# Buffers.net
KiCad netlist of a schematic drawn in Altium Designer
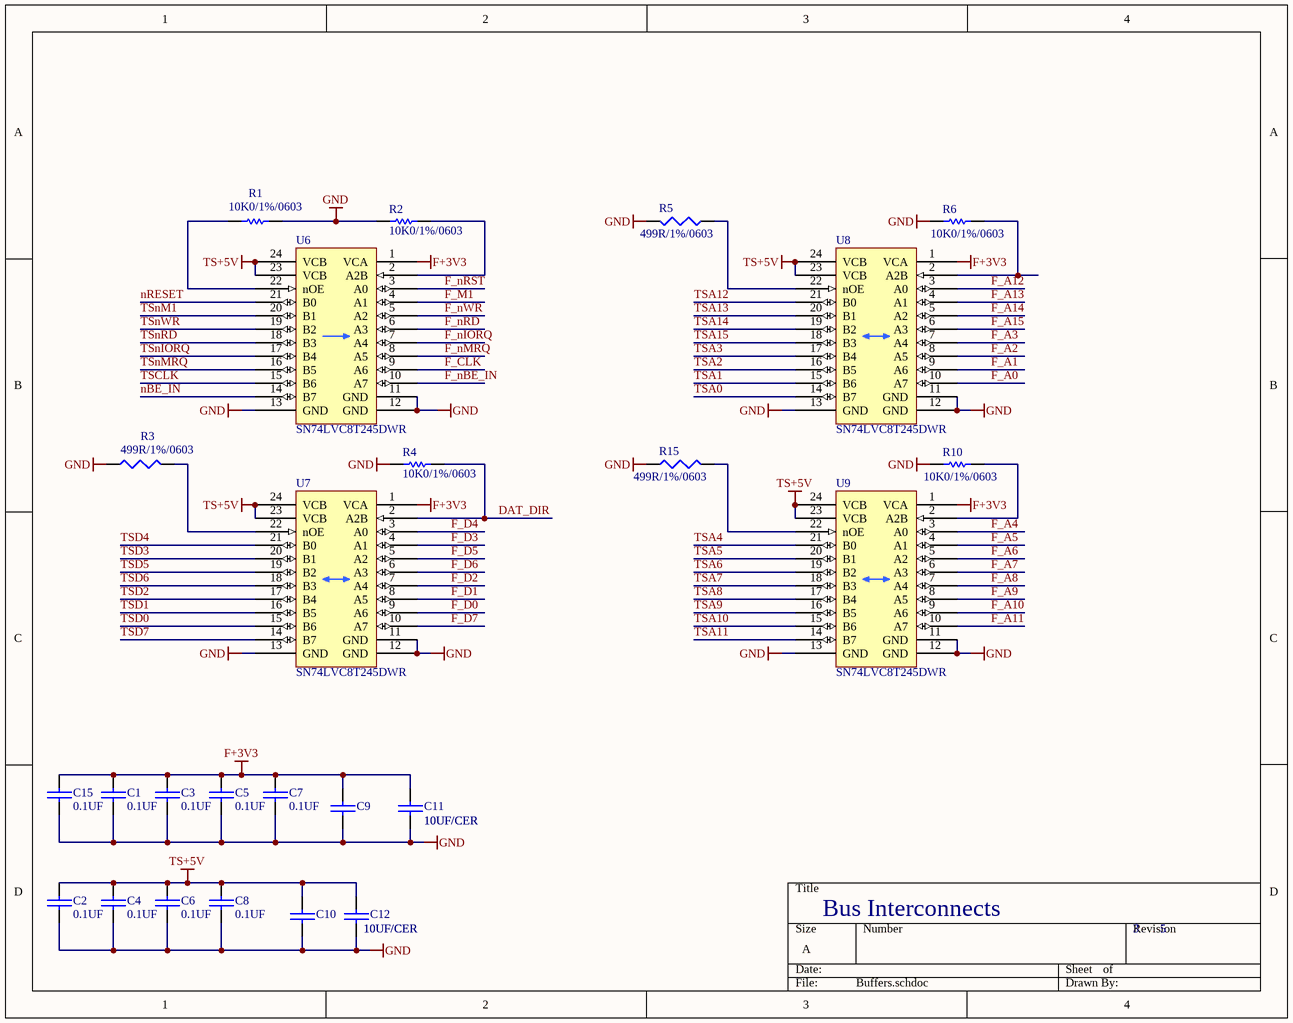
[diagram p0: Buffers.schdoc]

(export (version "E")
  (design (tool "Eeschema 10.0.6"))
  (components
    (comp (ref "C1")
      (value "0.1UF")
      (footprint "0603")
      (description "CAP .10UF 16V CERAMIC X7R 0603")
      (fields (field (name "MFG") "Kemet"))
      (libsource (lib "C64Interface") (part "0.1UF"))
    )
    (comp (ref "C2")
      (value "0.1UF")
      (footprint "0603")
      (description "CAP .10UF 16V CERAMIC X7R 0603")
      (fields (field (name "MFG") "Kemet"))
      (libsource (lib "C64Interface") (part "0.1UF"))
    )
    (comp (ref "C3")
      (value "0.1UF")
      (footprint "0603")
      (description "CAP .10UF 16V CERAMIC X7R 0603")
      (fields (field (name "MFG") "Kemet"))
      (libsource (lib "C64Interface") (part "0.1UF"))
    )
    (comp (ref "C4")
      (value "0.1UF")
      (footprint "0603")
      (description "CAP .10UF 16V CERAMIC X7R 0603")
      (fields (field (name "MFG") "Kemet"))
      (libsource (lib "C64Interface") (part "0.1UF"))
    )
    (comp (ref "C5")
      (value "0.1UF")
      (footprint "0603")
      (description "CAP .10UF 16V CERAMIC X7R 0603")
      (fields (field (name "MFG") "Kemet"))
      (libsource (lib "C64Interface") (part "0.1UF"))
    )
    (comp (ref "C6")
      (value "0.1UF")
      (footprint "0603")
      (description "CAP .10UF 16V CERAMIC X7R 0603")
      (fields (field (name "MFG") "Kemet"))
      (libsource (lib "C64Interface") (part "0.1UF"))
    )
    (comp (ref "C7")
      (value "0.1UF")
      (footprint "0603")
      (description "CAP .10UF 16V CERAMIC X7R 0603")
      (fields (field (name "MFG") "Kemet"))
      (libsource (lib "C64Interface") (part "0.1UF"))
    )
    (comp (ref "C8")
      (value "0.1UF")
      (footprint "0603")
      (description "CAP .10UF 16V CERAMIC X7R 0603")
      (fields (field (name "MFG") "Kemet"))
      (libsource (lib "C64Interface") (part "0.1UF"))
    )
    (comp (ref "C9")
      (value "10UF/CER")
      (footprint "0805")
      (description "10µF ±10% 25V Ceramic Capacitor X7S 0805")
      (fields (field (name "MFG") "Murata"))
      (libsource (lib "Capacitors") (part "10UF/CER"))
    )
    (comp (ref "C10")
      (value "10UF/CER")
      (footprint "0805")
      (description "10µF ±10% 25V Ceramic Capacitor X7S 0805")
      (fields (field (name "MFG") "Murata"))
      (libsource (lib "Capacitors") (part "10UF/CER"))
    )
    (comp (ref "C11")
      (value "10UF/CER")
      (footprint "0805")
      (description "10µF ±10% 25V Ceramic Capacitor X7S 0805")
      (fields (field (name "MFG") "Murata"))
      (libsource (lib "Capacitors") (part "10UF/CER"))
    )
    (comp (ref "C12")
      (value "10UF/CER")
      (footprint "0805")
      (description "10µF ±10% 25V Ceramic Capacitor X7S 0805")
      (fields (field (name "MFG") "Murata"))
      (libsource (lib "Capacitors") (part "10UF/CER"))
    )
    (comp (ref "C15")
      (value "0.1UF")
      (footprint "0603")
      (description "CAP .10UF 16V CERAMIC X7R 0603")
      (fields (field (name "MFG") "Kemet"))
      (libsource (lib "C64Interface") (part "0.1UF"))
    )
    (comp (ref "R1")
      (value "10K0/1%/0603")
      (footprint "0603")
      (description "10k Ohm ±1% 0.1W, 1/10W Chip Resistor 0603 (1608 Metric) Moisture Resistant Thick Film")
      (fields (field (name "MFG") "Yageo"))
      (libsource (lib "Resistors") (part "RES10K0"))
    )
    (comp (ref "R2")
      (value "10K0/1%/0603")
      (footprint "0603")
      (description "10k Ohm ±1% 0.1W, 1/10W Chip Resistor 0603 (1608 Metric) Moisture Resistant Thick Film")
      (fields (field (name "MFG") "Yageo"))
      (libsource (lib "Resistors") (part "RES10K0"))
    )
    (comp (ref "R3")
      (value "499R/1%/0603")
      (footprint "0603")
      (description "499 Ohms ±1% 0.1W, 1/10W Chip Resistor 0603 (1608 Metric) Moisture Resistant Thick Film")
      (fields (field (name "MFG") "Yeago"))
      (libsource (lib "Resistors") (part "499R/1%/0603"))
    )
    (comp (ref "R4")
      (value "10K0/1%/0603")
      (footprint "0603")
      (description "10k Ohm ±1% 0.1W, 1/10W Chip Resistor 0603 (1608 Metric) Moisture Resistant Thick Film")
      (fields (field (name "MFG") "Yageo"))
      (libsource (lib "Resistors") (part "RES10K0"))
    )
    (comp (ref "R5")
      (value "499R/1%/0603")
      (footprint "0603")
      (description "499 Ohms ±1% 0.1W, 1/10W Chip Resistor 0603 (1608 Metric) Moisture Resistant Thick Film")
      (fields (field (name "MFG") "Yeago"))
      (libsource (lib "Resistors") (part "499R/1%/0603"))
    )
    (comp (ref "R6")
      (value "10K0/1%/0603")
      (footprint "0603")
      (description "10k Ohm ±1% 0.1W, 1/10W Chip Resistor 0603 (1608 Metric) Moisture Resistant Thick Film")
      (fields (field (name "MFG") "Yageo"))
      (libsource (lib "Resistors") (part "RES10K0"))
    )
    (comp (ref "R10")
      (value "10K0/1%/0603")
      (footprint "0603")
      (description "10k Ohm ±1% 0.1W, 1/10W Chip Resistor 0603 (1608 Metric) Moisture Resistant Thick Film")
      (fields (field (name "MFG") "Yageo"))
      (libsource (lib "Resistors") (part "RES10K0"))
    )
    (comp (ref "R15")
      (value "499R/1%/0603")
      (footprint "0603")
      (description "499 Ohms ±1% 0.1W, 1/10W Chip Resistor 0603 (1608 Metric) Moisture Resistant Thick Film")
      (fields (field (name "MFG") "Yeago"))
      (libsource (lib "Resistors") (part "499R/1%/0603"))
    )
    (comp (ref "U6")
      (value "SN74LVC8T245DWR")
      (footprint "SOL-24")
      (description "Voltage Level Translator Bidirectional 1 Circuit 8 Channel 24-SOIC")
      (fields (field (name "MFG") "TI"))
      (libsource (lib "DigitalIC") (part "SN74LVC8T245DWR"))
    )
    (comp (ref "U7")
      (value "SN74LVC8T245DWR")
      (footprint "SOL-24")
      (description "Voltage Level Translator Bidirectional 1 Circuit 8 Channel 24-SOIC")
      (fields (field (name "MFG") "TI"))
      (libsource (lib "DigitalIC") (part "SN74LVC8T245DWR"))
    )
    (comp (ref "U8")
      (value "SN74LVC8T245DWR")
      (footprint "SOL-24")
      (description "Voltage Level Translator Bidirectional 1 Circuit 8 Channel 24-SOIC")
      (fields (field (name "MFG") "TI"))
      (libsource (lib "DigitalIC") (part "SN74LVC8T245DWR"))
    )
    (comp (ref "U9")
      (value "SN74LVC8T245DWR")
      (footprint "SOL-24")
      (description "Voltage Level Translator Bidirectional 1 Circuit 8 Channel 24-SOIC")
      (fields (field (name "MFG") "TI"))
      (libsource (lib "DigitalIC") (part "SN74LVC8T245DWR"))
    )
  )
  (nets
    (net (code "1") (name "/DAT_DIR") (class "Default")
      (node (ref "R4") (pin "2") (pinfunction "2_2") (pintype "passive"))
      (node (ref "U7") (pin "2") (pinfunction "A2B_2") (pintype "input"))
    )
    (net (code "2") (name "/F_A0") (class "Default")
      (node (ref "U8") (pin "10") (pinfunction "A7_10") (pintype "bidirectional"))
    )
    (net (code "3") (name "/F_A1") (class "Default")
      (node (ref "U8") (pin "9") (pinfunction "A6_9") (pintype "bidirectional"))
    )
    (net (code "4") (name "/F_A2") (class "Default")
      (node (ref "U8") (pin "8") (pinfunction "A5_8") (pintype "bidirectional"))
    )
    (net (code "5") (name "/F_A3") (class "Default")
      (node (ref "U8") (pin "7") (pinfunction "A4_7") (pintype "bidirectional"))
    )
    (net (code "6") (name "/F_A4") (class "Default")
      (node (ref "U9") (pin "3") (pinfunction "A0_3") (pintype "bidirectional"))
    )
    (net (code "7") (name "/F_A5") (class "Default")
      (node (ref "U9") (pin "4") (pinfunction "A1_4") (pintype "bidirectional"))
    )
    (net (code "8") (name "/F_A6") (class "Default")
      (node (ref "U9") (pin "5") (pinfunction "A2_5") (pintype "bidirectional"))
    )
    (net (code "9") (name "/F_A7") (class "Default")
      (node (ref "U9") (pin "6") (pinfunction "A3_6") (pintype "bidirectional"))
    )
    (net (code "10") (name "/F_A8") (class "Default")
      (node (ref "U9") (pin "7") (pinfunction "A4_7") (pintype "bidirectional"))
    )
    (net (code "11") (name "/F_A9") (class "Default")
      (node (ref "U9") (pin "8") (pinfunction "A5_8") (pintype "bidirectional"))
    )
    (net (code "12") (name "/F_A10") (class "Default")
      (node (ref "U9") (pin "9") (pinfunction "A6_9") (pintype "bidirectional"))
    )
    (net (code "13") (name "/F_A11") (class "Default")
      (node (ref "U9") (pin "10") (pinfunction "A7_10") (pintype "bidirectional"))
    )
    (net (code "14") (name "/F_A12") (class "Default")
      (node (ref "U8") (pin "3") (pinfunction "A0_3") (pintype "bidirectional"))
    )
    (net (code "15") (name "/F_A13") (class "Default")
      (node (ref "U8") (pin "4") (pinfunction "A1_4") (pintype "bidirectional"))
    )
    (net (code "16") (name "/F_A14") (class "Default")
      (node (ref "U8") (pin "5") (pinfunction "A2_5") (pintype "bidirectional"))
    )
    (net (code "17") (name "/F_A15") (class "Default")
      (node (ref "U8") (pin "6") (pinfunction "A3_6") (pintype "bidirectional"))
    )
    (net (code "18") (name "/F_CLK") (class "Default")
      (node (ref "U6") (pin "9") (pinfunction "A6_9") (pintype "bidirectional"))
    )
    (net (code "19") (name "/F_D0") (class "Default")
      (node (ref "U7") (pin "9") (pinfunction "A6_9") (pintype "bidirectional"))
    )
    (net (code "20") (name "/F_D1") (class "Default")
      (node (ref "U7") (pin "8") (pinfunction "A5_8") (pintype "bidirectional"))
    )
    (net (code "21") (name "/F_D2") (class "Default")
      (node (ref "U7") (pin "7") (pinfunction "A4_7") (pintype "bidirectional"))
    )
    (net (code "22") (name "/F_D3") (class "Default")
      (node (ref "U7") (pin "4") (pinfunction "A1_4") (pintype "bidirectional"))
    )
    (net (code "23") (name "/F_D4") (class "Default")
      (node (ref "U7") (pin "3") (pinfunction "A0_3") (pintype "bidirectional"))
    )
    (net (code "24") (name "/F_D5") (class "Default")
      (node (ref "U7") (pin "5") (pinfunction "A2_5") (pintype "bidirectional"))
    )
    (net (code "25") (name "/F_D6") (class "Default")
      (node (ref "U7") (pin "6") (pinfunction "A3_6") (pintype "bidirectional"))
    )
    (net (code "26") (name "/F_D7") (class "Default")
      (node (ref "U7") (pin "10") (pinfunction "A7_10") (pintype "bidirectional"))
    )
    (net (code "27") (name "/F_M1") (class "Default")
      (node (ref "U6") (pin "4") (pinfunction "A1_4") (pintype "bidirectional"))
    )
    (net (code "28") (name "/F_nBE_IN") (class "Default")
      (node (ref "U6") (pin "10") (pinfunction "A7_10") (pintype "bidirectional"))
    )
    (net (code "29") (name "/F_nIORQ") (class "Default")
      (node (ref "U6") (pin "7") (pinfunction "A4_7") (pintype "bidirectional"))
    )
    (net (code "30") (name "/F_nMRQ") (class "Default")
      (node (ref "U6") (pin "8") (pinfunction "A5_8") (pintype "bidirectional"))
    )
    (net (code "31") (name "/F_nRD") (class "Default")
      (node (ref "U6") (pin "6") (pinfunction "A3_6") (pintype "bidirectional"))
    )
    (net (code "32") (name "/F_nRST") (class "Default")
      (node (ref "U6") (pin "3") (pinfunction "A0_3") (pintype "bidirectional"))
    )
    (net (code "33") (name "/F_nWR") (class "Default")
      (node (ref "U6") (pin "5") (pinfunction "A2_5") (pintype "bidirectional"))
    )
    (net (code "34") (name "/TSA0") (class "Default")
      (node (ref "U8") (pin "14") (pinfunction "B7_14") (pintype "bidirectional"))
    )
    (net (code "35") (name "/TSA1") (class "Default")
      (node (ref "U8") (pin "15") (pinfunction "B6_15") (pintype "bidirectional"))
    )
    (net (code "36") (name "/TSA2") (class "Default")
      (node (ref "U8") (pin "16") (pinfunction "B5_16") (pintype "bidirectional"))
    )
    (net (code "37") (name "/TSA3") (class "Default")
      (node (ref "U8") (pin "17") (pinfunction "B4_17") (pintype "bidirectional"))
    )
    (net (code "38") (name "/TSA4") (class "Default")
      (node (ref "U9") (pin "21") (pinfunction "B0_21") (pintype "bidirectional"))
    )
    (net (code "39") (name "/TSA5") (class "Default")
      (node (ref "U9") (pin "20") (pinfunction "B1_20") (pintype "bidirectional"))
    )
    (net (code "40") (name "/TSA6") (class "Default")
      (node (ref "U9") (pin "19") (pinfunction "B2_19") (pintype "bidirectional"))
    )
    (net (code "41") (name "/TSA7") (class "Default")
      (node (ref "U9") (pin "18") (pinfunction "B3_18") (pintype "bidirectional"))
    )
    (net (code "42") (name "/TSA8") (class "Default")
      (node (ref "U9") (pin "17") (pinfunction "B4_17") (pintype "bidirectional"))
    )
    (net (code "43") (name "/TSA9") (class "Default")
      (node (ref "U9") (pin "16") (pinfunction "B5_16") (pintype "bidirectional"))
    )
    (net (code "44") (name "/TSA10") (class "Default")
      (node (ref "U9") (pin "15") (pinfunction "B6_15") (pintype "bidirectional"))
    )
    (net (code "45") (name "/TSA11") (class "Default")
      (node (ref "U9") (pin "14") (pinfunction "B7_14") (pintype "bidirectional"))
    )
    (net (code "46") (name "/TSA12") (class "Default")
      (node (ref "U8") (pin "21") (pinfunction "B0_21") (pintype "bidirectional"))
    )
    (net (code "47") (name "/TSA13") (class "Default")
      (node (ref "U8") (pin "20") (pinfunction "B1_20") (pintype "bidirectional"))
    )
    (net (code "48") (name "/TSA14") (class "Default")
      (node (ref "U8") (pin "19") (pinfunction "B2_19") (pintype "bidirectional"))
    )
    (net (code "49") (name "/TSA15") (class "Default")
      (node (ref "U8") (pin "18") (pinfunction "B3_18") (pintype "bidirectional"))
    )
    (net (code "50") (name "/TSCLK") (class "Default")
      (node (ref "U6") (pin "15") (pinfunction "B6_15") (pintype "bidirectional"))
    )
    (net (code "51") (name "/TSD0") (class "Default")
      (node (ref "U7") (pin "15") (pinfunction "B6_15") (pintype "bidirectional"))
    )
    (net (code "52") (name "/TSD1") (class "Default")
      (node (ref "U7") (pin "16") (pinfunction "B5_16") (pintype "bidirectional"))
    )
    (net (code "53") (name "/TSD2") (class "Default")
      (node (ref "U7") (pin "17") (pinfunction "B4_17") (pintype "bidirectional"))
    )
    (net (code "54") (name "/TSD3") (class "Default")
      (node (ref "U7") (pin "20") (pinfunction "B1_20") (pintype "bidirectional"))
    )
    (net (code "55") (name "/TSD4") (class "Default")
      (node (ref "U7") (pin "21") (pinfunction "B0_21") (pintype "bidirectional"))
    )
    (net (code "56") (name "/TSD5") (class "Default")
      (node (ref "U7") (pin "19") (pinfunction "B2_19") (pintype "bidirectional"))
    )
    (net (code "57") (name "/TSD6") (class "Default")
      (node (ref "U7") (pin "18") (pinfunction "B3_18") (pintype "bidirectional"))
    )
    (net (code "58") (name "/TSD7") (class "Default")
      (node (ref "U7") (pin "14") (pinfunction "B7_14") (pintype "bidirectional"))
    )
    (net (code "59") (name "/TSnIORQ") (class "Default")
      (node (ref "U6") (pin "17") (pinfunction "B4_17") (pintype "bidirectional"))
    )
    (net (code "60") (name "/TSnM1") (class "Default")
      (node (ref "U6") (pin "20") (pinfunction "B1_20") (pintype "bidirectional"))
    )
    (net (code "61") (name "/TSnMRQ") (class "Default")
      (node (ref "U6") (pin "16") (pinfunction "B5_16") (pintype "bidirectional"))
    )
    (net (code "62") (name "/TSnRD") (class "Default")
      (node (ref "U6") (pin "18") (pinfunction "B3_18") (pintype "bidirectional"))
    )
    (net (code "63") (name "/TSnWR") (class "Default")
      (node (ref "U6") (pin "19") (pinfunction "B2_19") (pintype "bidirectional"))
    )
    (net (code "64") (name "/nBE_IN") (class "Default")
      (node (ref "U6") (pin "14") (pinfunction "B7_14") (pintype "bidirectional"))
    )
    (net (code "65") (name "/nRESET") (class "Default")
      (node (ref "U6") (pin "21") (pinfunction "B0_21") (pintype "bidirectional"))
    )
    (net (code "66") (name "F+3V3") (class "Default")
      (node (ref "C1") (pin "1") (pintype "passive"))
      (node (ref "C11") (pin "1") (pintype "passive"))
      (node (ref "C15") (pin "1") (pintype "passive"))
      (node (ref "C3") (pin "1") (pintype "passive"))
      (node (ref "C5") (pin "1") (pintype "passive"))
      (node (ref "C7") (pin "1") (pintype "passive"))
      (node (ref "C9") (pin "1") (pintype "passive"))
      (node (ref "U6") (pin "1") (pinfunction "VCA_1") (pintype "power_in"))
      (node (ref "U7") (pin "1") (pinfunction "VCA_1") (pintype "power_in"))
      (node (ref "U8") (pin "1") (pinfunction "VCA_1") (pintype "power_in"))
      (node (ref "U9") (pin "1") (pinfunction "VCA_1") (pintype "power_in"))
    )
    (net (code "67") (name "GND") (class "Default")
      (node (ref "C1") (pin "2") (pintype "passive"))
      (node (ref "C10") (pin "2") (pintype "passive"))
      (node (ref "C11") (pin "2") (pintype "passive"))
      (node (ref "C12") (pin "2") (pintype "passive"))
      (node (ref "C15") (pin "2") (pintype "passive"))
      (node (ref "C2") (pin "2") (pintype "passive"))
      (node (ref "C3") (pin "2") (pintype "passive"))
      (node (ref "C4") (pin "2") (pintype "passive"))
      (node (ref "C5") (pin "2") (pintype "passive"))
      (node (ref "C6") (pin "2") (pintype "passive"))
      (node (ref "C7") (pin "2") (pintype "passive"))
      (node (ref "C8") (pin "2") (pintype "passive"))
      (node (ref "C9") (pin "2") (pintype "passive"))
      (node (ref "R1") (pin "1") (pinfunction "1_1") (pintype "passive"))
      (node (ref "R10") (pin "1") (pinfunction "1_1") (pintype "passive"))
      (node (ref "R15") (pin "1") (pintype "passive"))
      (node (ref "R2") (pin "1") (pinfunction "1_1") (pintype "passive"))
      (node (ref "R3") (pin "1") (pintype "passive"))
      (node (ref "R4") (pin "1") (pinfunction "1_1") (pintype "passive"))
      (node (ref "R5") (pin "2") (pintype "passive"))
      (node (ref "R6") (pin "1") (pinfunction "1_1") (pintype "passive"))
      (node (ref "U6") (pin "11") (pinfunction "GND_11") (pintype "power_in"))
      (node (ref "U6") (pin "12") (pinfunction "GND_12") (pintype "power_in"))
      (node (ref "U6") (pin "13") (pinfunction "GND_13") (pintype "power_in"))
      (node (ref "U7") (pin "11") (pinfunction "GND_11") (pintype "power_in"))
      (node (ref "U7") (pin "12") (pinfunction "GND_12") (pintype "power_in"))
      (node (ref "U7") (pin "13") (pinfunction "GND_13") (pintype "power_in"))
      (node (ref "U8") (pin "11") (pinfunction "GND_11") (pintype "power_in"))
      (node (ref "U8") (pin "12") (pinfunction "GND_12") (pintype "power_in"))
      (node (ref "U8") (pin "13") (pinfunction "GND_13") (pintype "power_in"))
      (node (ref "U9") (pin "11") (pinfunction "GND_11") (pintype "power_in"))
      (node (ref "U9") (pin "12") (pinfunction "GND_12") (pintype "power_in"))
      (node (ref "U9") (pin "13") (pinfunction "GND_13") (pintype "power_in"))
    )
    (net (code "68") (name "Net-(U6-A2B)") (class "Default")
      (node (ref "R2") (pin "2") (pinfunction "2_2") (pintype "passive"))
      (node (ref "U6") (pin "2") (pinfunction "A2B_2") (pintype "input"))
    )
    (net (code "69") (name "Net-(U6-nOE)") (class "Default")
      (node (ref "R1") (pin "2") (pinfunction "2_2") (pintype "passive"))
      (node (ref "U6") (pin "22") (pinfunction "nOE_22") (pintype "input"))
    )
    (net (code "70") (name "Net-(U7-nOE)") (class "Default")
      (node (ref "R3") (pin "2") (pintype "passive"))
      (node (ref "U7") (pin "22") (pinfunction "nOE_22") (pintype "input"))
    )
    (net (code "71") (name "Net-(U8-A2B)") (class "Default")
      (node (ref "R6") (pin "2") (pinfunction "2_2") (pintype "passive"))
      (node (ref "U8") (pin "2") (pinfunction "A2B_2") (pintype "input"))
    )
    (net (code "72") (name "Net-(U8-nOE)") (class "Default")
      (node (ref "R5") (pin "1") (pintype "passive"))
      (node (ref "U8") (pin "22") (pinfunction "nOE_22") (pintype "input"))
    )
    (net (code "73") (name "Net-(U9-A2B)") (class "Default")
      (node (ref "R10") (pin "2") (pinfunction "2_2") (pintype "passive"))
      (node (ref "U9") (pin "2") (pinfunction "A2B_2") (pintype "input"))
    )
    (net (code "74") (name "Net-(U9-nOE)") (class "Default")
      (node (ref "R15") (pin "2") (pintype "passive"))
      (node (ref "U9") (pin "22") (pinfunction "nOE_22") (pintype "input"))
    )
    (net (code "75") (name "TS+5V") (class "Default")
      (node (ref "C10") (pin "1") (pintype "passive"))
      (node (ref "C12") (pin "1") (pintype "passive"))
      (node (ref "C2") (pin "1") (pintype "passive"))
      (node (ref "C4") (pin "1") (pintype "passive"))
      (node (ref "C6") (pin "1") (pintype "passive"))
      (node (ref "C8") (pin "1") (pintype "passive"))
      (node (ref "U6") (pin "23") (pinfunction "VCB_23") (pintype "power_in"))
      (node (ref "U6") (pin "24") (pinfunction "VCB_24") (pintype "power_in"))
      (node (ref "U7") (pin "23") (pinfunction "VCB_23") (pintype "power_in"))
      (node (ref "U7") (pin "24") (pinfunction "VCB_24") (pintype "power_in"))
      (node (ref "U8") (pin "23") (pinfunction "VCB_23") (pintype "power_in"))
      (node (ref "U8") (pin "24") (pinfunction "VCB_24") (pintype "power_in"))
      (node (ref "U9") (pin "23") (pinfunction "VCB_23") (pintype "power_in"))
      (node (ref "U9") (pin "24") (pinfunction "VCB_24") (pintype "power_in"))
    )
  )
)
